# Grove_-_Temperature_sensor_v1_1.net
KiCad netlist of a schematic drawn in EAGLE
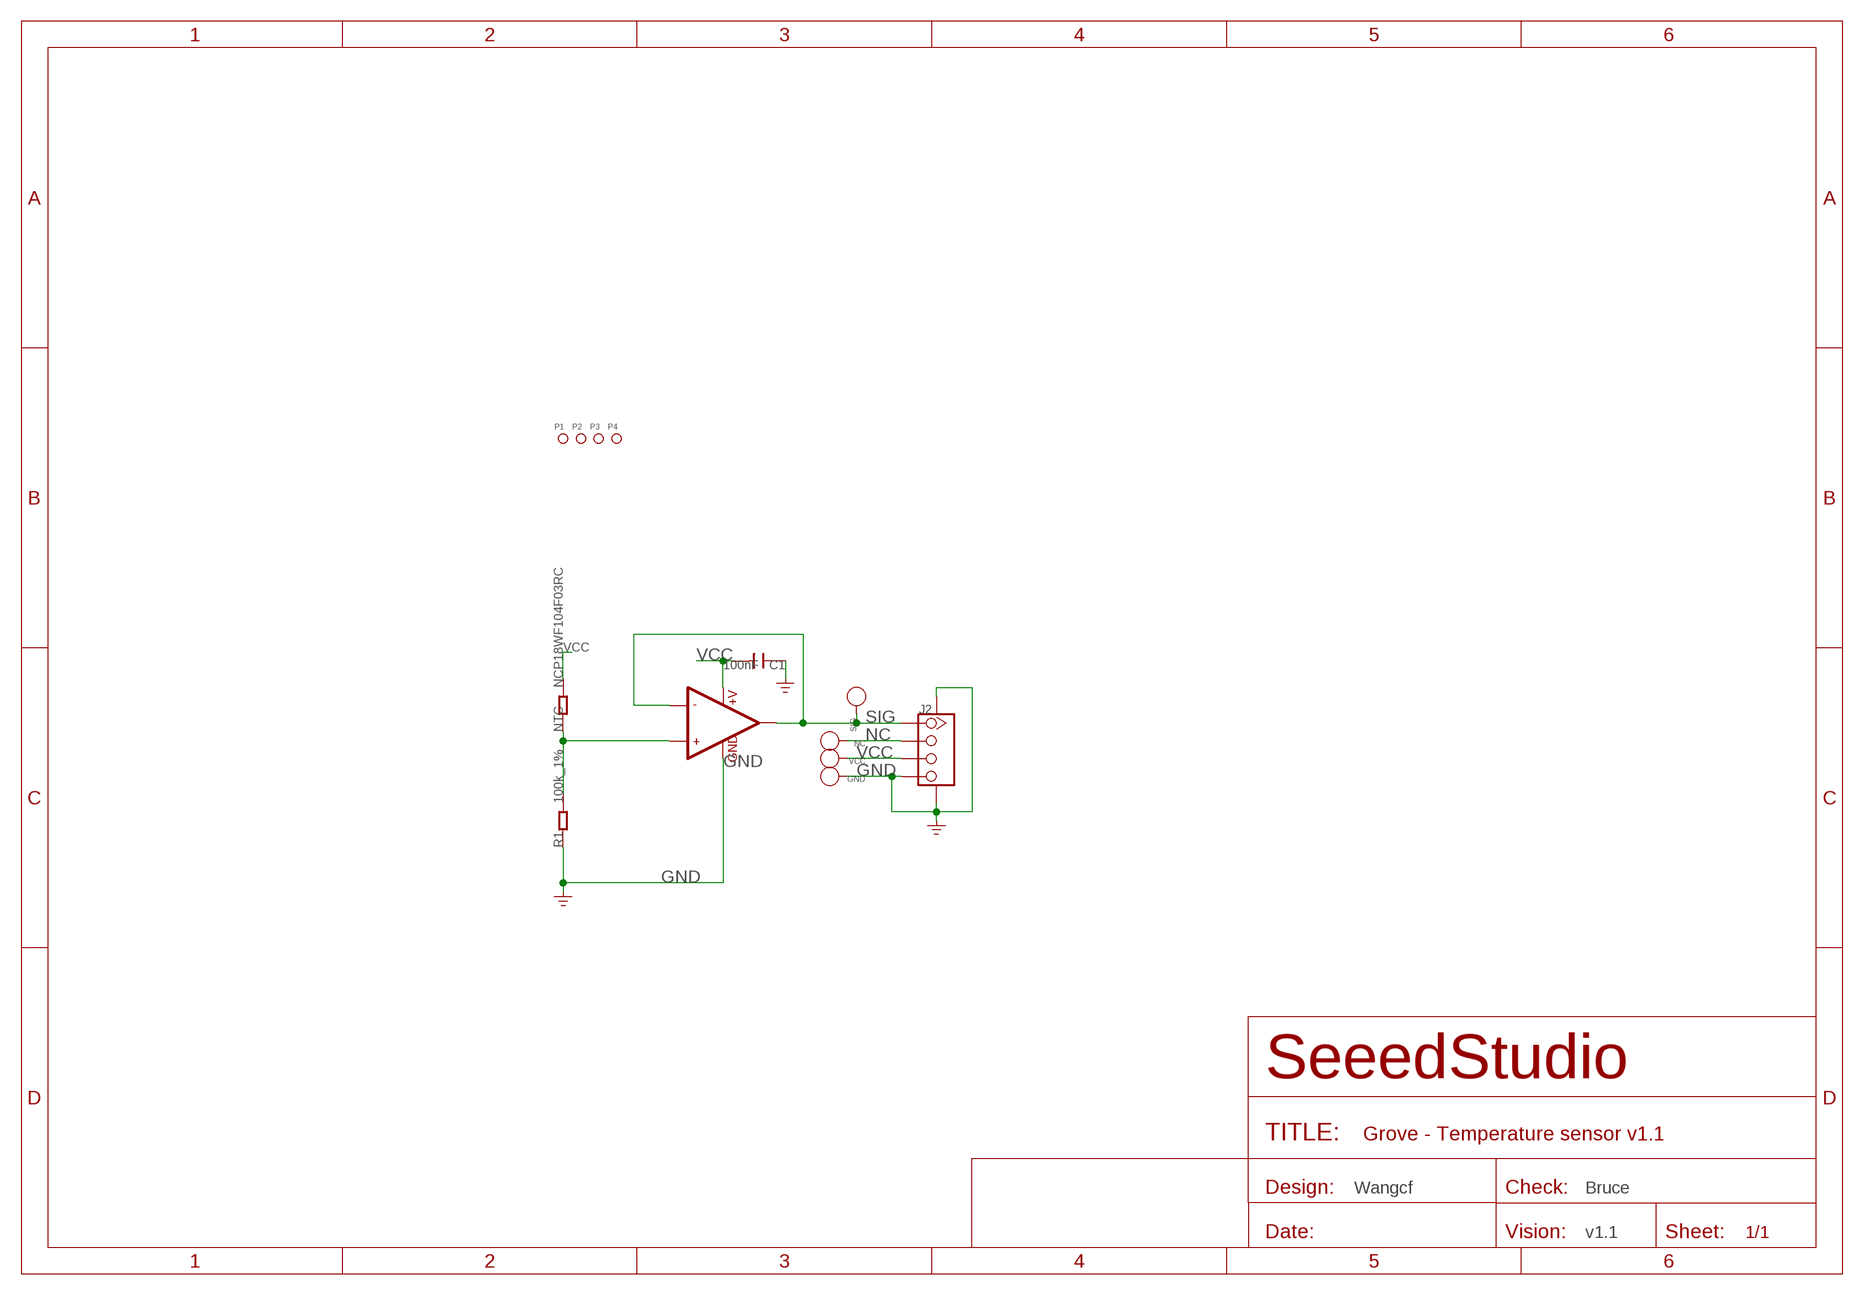
[diagram p0: schematic, sheet 1]

(export (version "E")
  (design (tool "Eeschema 10.0.6"))
  (components
    (comp (ref "C1")
      (value "100nF")
      (footprint "eagle-import:C0603")
      (libsource (lib "eagle-import") (part "C-0603"))
    )
    (comp (ref "GND")
      (value "PAD-TEST-POINT'4545'")
      (footprint "eagle-import:TP_4545")
      (fields (field (name "PARTNO") "DNP"))
      (libsource (lib "eagle-import") (part "PAD-TEST-POINT'4545'"))
    )
    (comp (ref "J2")
      (value "TWIG-4P-2.0-SMD-FEMALE-REINFORCE'DD'")
      (footprint "eagle-import:4P-SMD-2.0")
      (libsource (lib "eagle-import") (part "TWIG-4P-2.0-SMD-FEMALE-REINFORCE'DD'"))
    )
    (comp (ref "NC")
      (value "PAD-TEST-POINT'4545'")
      (footprint "eagle-import:TP_4545")
      (fields (field (name "PARTNO") "DNP"))
      (libsource (lib "eagle-import") (part "PAD-TEST-POINT'4545'"))
    )
    (comp (ref "NTC")
      (value "NCP18WF104F03RC")
      (footprint "eagle-import:R0603")
      (libsource (lib "eagle-import") (part "R-0603"))
    )
    (comp (ref "P1")
      (value "PAD-MARK")
      (footprint "eagle-import:ROUND-MARK-1.0")
      (fields (field (name "PARTNO") "DNP"))
      (libsource (lib "eagle-import") (part "PAD-MARK"))
    )
    (comp (ref "P2")
      (value "PAD-MARK")
      (footprint "eagle-import:ROUND-MARK-1.0")
      (fields (field (name "PARTNO") "DNP"))
      (libsource (lib "eagle-import") (part "PAD-MARK"))
    )
    (comp (ref "P3")
      (value "PAD-MARK")
      (footprint "eagle-import:ROUND-MARK-1.0")
      (fields (field (name "PARTNO") "DNP"))
      (libsource (lib "eagle-import") (part "PAD-MARK"))
    )
    (comp (ref "P4")
      (value "PAD-MARK")
      (footprint "eagle-import:ROUND-MARK-1.0")
      (fields (field (name "PARTNO") "DNP"))
      (libsource (lib "eagle-import") (part "PAD-MARK"))
    )
    (comp (ref "R1")
      (value "100k_1%")
      (footprint "eagle-import:R0603")
      (libsource (lib "eagle-import") (part "R-0603"))
    )
    (comp (ref "SIG")
      (value "PAD-TEST-POINT'4545'")
      (footprint "eagle-import:TP_4545")
      (fields (field (name "PARTNO") "DNP"))
      (libsource (lib "eagle-import") (part "PAD-TEST-POINT'4545'"))
    )
    (comp (ref "U1")
      (value "LM358DR")
      (footprint "eagle-import:SO08")
      (libsource (lib "eagle-import") (part "LMV358"))
    )
    (comp (ref "VCC")
      (value "PAD-TEST-POINT'4545'")
      (footprint "eagle-import:TP_4545")
      (fields (field (name "PARTNO") "DNP"))
      (libsource (lib "eagle-import") (part "PAD-TEST-POINT'4545'"))
    )
  )
  (nets
    (net (code "1") (name "/NC") (class "Default")
      (node (ref "J2") (pin "2") (pinfunction "2_2") (pintype "bidirectional"))
      (node (ref "NC") (pin "T") (pinfunction "T_T") (pintype "bidirectional"))
    )
    (net (code "2") (name "/SIG") (class "Default")
      (node (ref "J2") (pin "1") (pinfunction "1_1") (pintype "bidirectional"))
      (node (ref "SIG") (pin "T") (pinfunction "T_T") (pintype "bidirectional"))
      (node (ref "U1") (pin "1") (pinfunction "OUT1_1") (pintype "output"))
      (node (ref "U1") (pin "2") (pinfunction "-IN1_2") (pintype "input"))
    )
    (net (code "3") (name "/VCC") (class "Default")
      (node (ref "C1") (pin "2") (pinfunction "2_2") (pintype "passive"))
      (node (ref "J2") (pin "3") (pinfunction "3_3") (pintype "bidirectional"))
      (node (ref "NTC") (pin "2") (pinfunction "2_2") (pintype "passive"))
      (node (ref "U1") (pin "8") (pinfunction "+V_8") (pintype "power_in"))
      (node (ref "VCC") (pin "T") (pinfunction "T_T") (pintype "bidirectional"))
    )
    (net (code "4") (name "GND_POWER") (class "Default")
      (node (ref "C1") (pin "1") (pinfunction "1_1") (pintype "passive"))
      (node (ref "GND") (pin "T") (pinfunction "T_T") (pintype "bidirectional"))
      (node (ref "J2") (pin "4") (pinfunction "4_4") (pintype "bidirectional"))
      (node (ref "J2") (pin "SS1") (pinfunction "SS1_SS1") (pintype "bidirectional"))
      (node (ref "J2") (pin "SS2") (pinfunction "SS2_SS2") (pintype "bidirectional"))
      (node (ref "R1") (pin "1") (pinfunction "1_1") (pintype "passive"))
      (node (ref "U1") (pin "4") (pinfunction "GND_4") (pintype "power_in"))
    )
    (net (code "5") (name "Net-(U1A-+IN1)") (class "Default")
      (node (ref "NTC") (pin "1") (pinfunction "1_1") (pintype "passive"))
      (node (ref "R1") (pin "2") (pinfunction "2_2") (pintype "passive"))
      (node (ref "U1") (pin "3") (pinfunction "+IN1_3") (pintype "input"))
    )
  )
)
